# Mainboard_2.net
KiCad netlist of a schematic drawn in Altium Designer
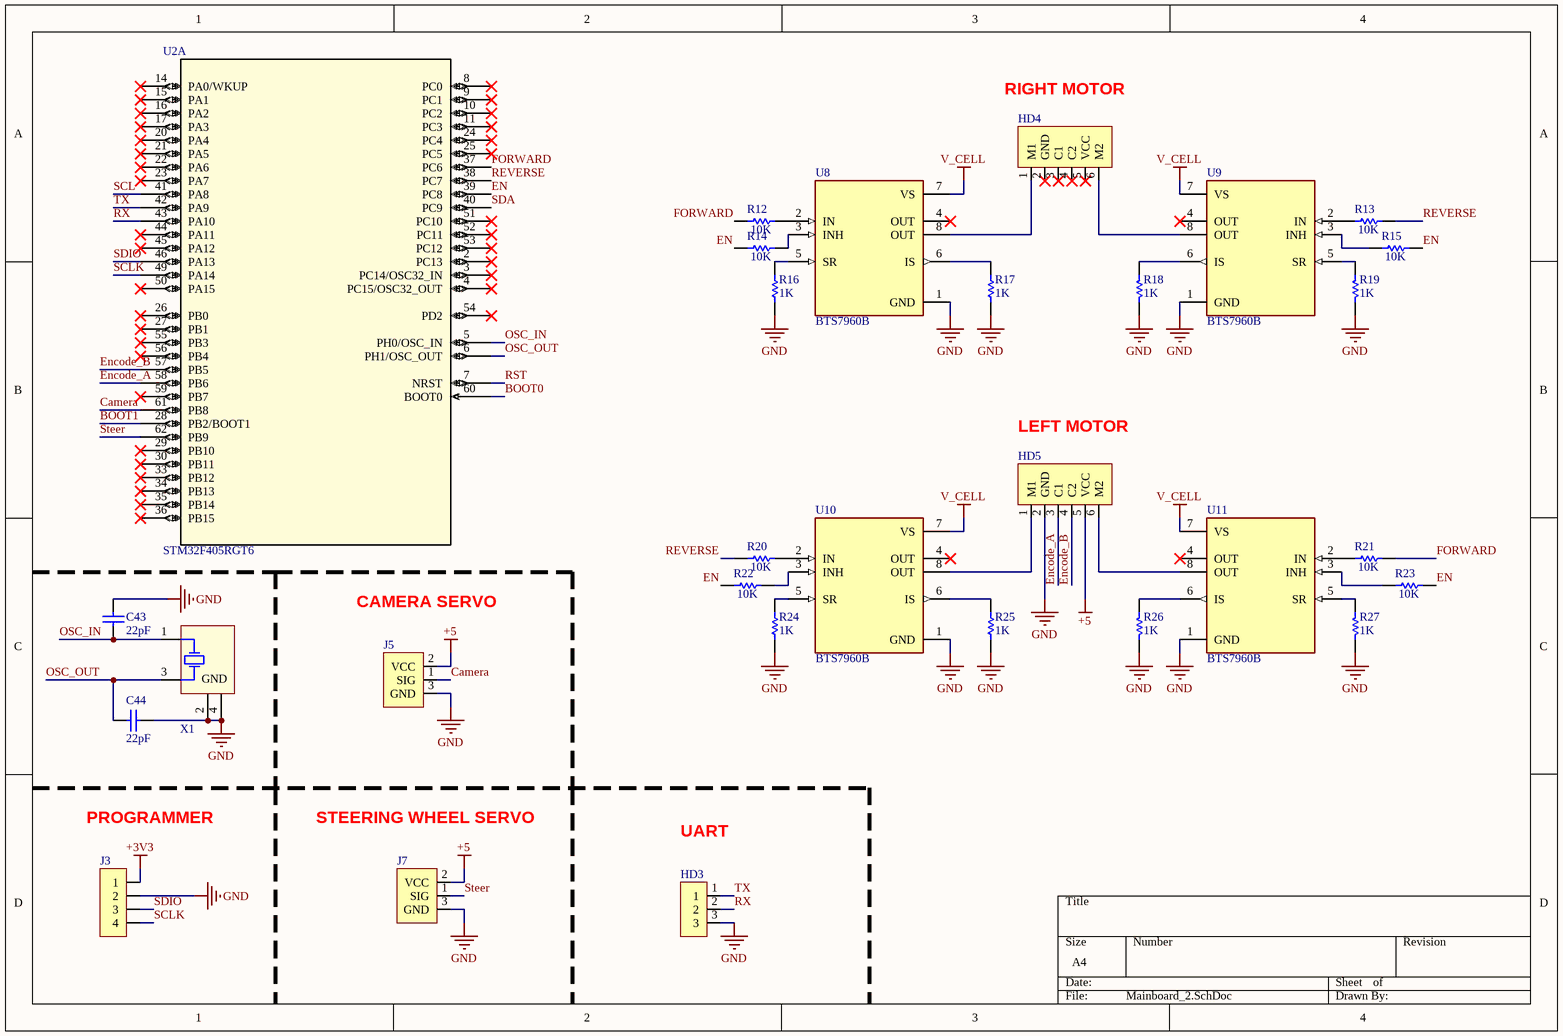
[diagram p0: Mainboard_2.SchDoc]

(export (version "E")
  (design (tool "Eeschema 10.0.6"))
  (components
    (comp (ref "C43")
      (value "22pF")
      (footprint "6-0805_M")
      (description "Capacitor")
      (fields (field (name "PUBLISHER") "Altium Limited"))
      (libsource (lib "Miscellaneous Devices") (part "Cap"))
    )
    (comp (ref "C44")
      (value "22pF")
      (footprint "6-0805_M")
      (description "Capacitor")
      (fields (field (name "PUBLISHER") "Altium Limited"))
      (libsource (lib "Miscellaneous Devices") (part "Cap"))
    )
    (comp (ref "HD3")
      (value "3_pin conn")
      (footprint "3-pin XHB_2.54")
      (libsource (lib "KHAI_LIB") (part "3_pin conn"))
    )
    (comp (ref "HD4")
      (value "6-pin connnector (Encoder DC motor 2mm)")
      (footprint "6_PIN MOTOR")
      (libsource (lib "KHAI_LIB") (part "6-pin connnector (Encoder DC motor 2.54mm)"))
    )
    (comp (ref "HD5")
      (value "6-pin connnector (Encoder DC motor 2mm)")
      (footprint "6_PIN MOTOR")
      (libsource (lib "KHAI_LIB") (part "6-pin connnector (Encoder DC motor 2.54mm)"))
    )
    (comp (ref "J3")
      (value "4_pin connector")
      (footprint "4_PIN 2.54mm")
      (libsource (lib "KHAI_LIB") (part "4_pin connector"))
    )
    (comp (ref "J5")
      (value "3_pin steering wheel")
      (footprint "3_PIN SERVO CONNECTOR")
      (libsource (lib "KHAI_LIB") (part "3_pin steering wheel"))
    )
    (comp (ref "J7")
      (value "3_pin steering wheel")
      (footprint "3_PIN SERVO CONNECTOR")
      (libsource (lib "KHAI_LIB") (part "3_pin steering wheel"))
    )
    (comp (ref "R12")
      (value "10K")
      (footprint "6-0805_N")
      (description "Resistor")
      (fields (field (name "PUBLISHER") "Altium Limited"))
      (libsource (lib "Miscellaneous Devices") (part "Res1"))
    )
    (comp (ref "R13")
      (value "10K")
      (footprint "6-0805_N")
      (description "Resistor")
      (fields (field (name "PUBLISHER") "Altium Limited"))
      (libsource (lib "Miscellaneous Devices") (part "Res1"))
    )
    (comp (ref "R14")
      (value "10K")
      (footprint "6-0805_N")
      (description "Resistor")
      (fields (field (name "PUBLISHER") "Altium Limited"))
      (libsource (lib "Miscellaneous Devices") (part "Res1"))
    )
    (comp (ref "R15")
      (value "10K")
      (footprint "6-0805_N")
      (description "Resistor")
      (fields (field (name "PUBLISHER") "Altium Limited"))
      (libsource (lib "Miscellaneous Devices") (part "Res1"))
    )
    (comp (ref "R16")
      (value "1K")
      (footprint "6-0805_N")
      (description "Resistor")
      (fields (field (name "PUBLISHER") "Altium Limited"))
      (libsource (lib "Miscellaneous Devices") (part "Res1"))
    )
    (comp (ref "R17")
      (value "1K")
      (footprint "6-0805_N")
      (description "Resistor")
      (fields (field (name "PUBLISHER") "Altium Limited"))
      (libsource (lib "Miscellaneous Devices") (part "Res1"))
    )
    (comp (ref "R18")
      (value "1K")
      (footprint "6-0805_N")
      (description "Resistor")
      (fields (field (name "PUBLISHER") "Altium Limited"))
      (libsource (lib "Miscellaneous Devices") (part "Res1"))
    )
    (comp (ref "R19")
      (value "1K")
      (footprint "6-0805_N")
      (description "Resistor")
      (fields (field (name "PUBLISHER") "Altium Limited"))
      (libsource (lib "Miscellaneous Devices") (part "Res1"))
    )
    (comp (ref "R20")
      (value "10K")
      (footprint "6-0805_N")
      (description "Resistor")
      (fields (field (name "PUBLISHER") "Altium Limited"))
      (libsource (lib "Miscellaneous Devices") (part "Res1"))
    )
    (comp (ref "R21")
      (value "10K")
      (footprint "6-0805_N")
      (description "Resistor")
      (fields (field (name "PUBLISHER") "Altium Limited"))
      (libsource (lib "Miscellaneous Devices") (part "Res1"))
    )
    (comp (ref "R22")
      (value "10K")
      (footprint "6-0805_N")
      (description "Resistor")
      (fields (field (name "PUBLISHER") "Altium Limited"))
      (libsource (lib "Miscellaneous Devices") (part "Res1"))
    )
    (comp (ref "R23")
      (value "10K")
      (footprint "6-0805_N")
      (description "Resistor")
      (fields (field (name "PUBLISHER") "Altium Limited"))
      (libsource (lib "Miscellaneous Devices") (part "Res1"))
    )
    (comp (ref "R24")
      (value "1K")
      (footprint "6-0805_N")
      (description "Resistor")
      (fields (field (name "PUBLISHER") "Altium Limited"))
      (libsource (lib "Miscellaneous Devices") (part "Res1"))
    )
    (comp (ref "R25")
      (value "1K")
      (footprint "6-0805_N")
      (description "Resistor")
      (fields (field (name "PUBLISHER") "Altium Limited"))
      (libsource (lib "Miscellaneous Devices") (part "Res1"))
    )
    (comp (ref "R26")
      (value "1K")
      (footprint "6-0805_N")
      (description "Resistor")
      (fields (field (name "PUBLISHER") "Altium Limited"))
      (libsource (lib "Miscellaneous Devices") (part "Res1"))
    )
    (comp (ref "R27")
      (value "1K")
      (footprint "6-0805_N")
      (description "Resistor")
      (fields (field (name "PUBLISHER") "Altium Limited"))
      (libsource (lib "Miscellaneous Devices") (part "Res1"))
    )
    (comp (ref "U2")
      (value "STM32F405RGT6")
      (footprint "LQFP64-10x10mm")
      (fields (field (name "COPYRIGHT") "Copyright (C) 2025 Ultra Librarian. All rights reserved."))
      (libsource (lib "STM32F405RGT6") (part "STM32F405RGT6"))
    )
    (comp (ref "U8")
      (value "BTS7960B")
      (footprint "DPAK127P1490X440-8N")
      (description "Half Bridge Driver DC Motors, General Purpose DMOS PG-TO263-7-1")
      (fields (field (name "MF") "Infineon"))
      (libsource (lib "") (part "BTS7960B_1"))
    )
    (comp (ref "U9")
      (value "BTS7960B")
      (footprint "DPAK127P1490X440-8N")
      (description "Half Bridge Driver DC Motors, General Purpose DMOS PG-TO263-7-1")
      (fields (field (name "MF") "Infineon"))
      (libsource (lib "KHAI_LIB") (part "BTS7960B"))
    )
    (comp (ref "U10")
      (value "BTS7960B")
      (footprint "DPAK127P1490X440-8N")
      (description "Half Bridge Driver DC Motors, General Purpose DMOS PG-TO263-7-1")
      (fields (field (name "MF") "Infineon"))
      (libsource (lib "") (part "BTS7960B_1"))
    )
    (comp (ref "U11")
      (value "BTS7960B")
      (footprint "DPAK127P1490X440-8N")
      (description "Half Bridge Driver DC Motors, General Purpose DMOS PG-TO263-7-1")
      (fields (field (name "MF") "Infineon"))
      (libsource (lib "KHAI_LIB") (part "BTS7960B"))
    )
    (comp (ref "X1")
      (value "XT4")
      (footprint "XT4-SMD")
      (description "Crystal, 16 MHz, -30 to 85 degC, 3.2 x 2.5 x 0.9 mm SMD")
      (libsource (lib "LIBRARY") (part "XT4"))
    )
  )
  (nets
    (net (code "1") (name "+3V3") (class "Default")
      (node (ref "J3") (pin "1") (pinfunction "1_1") (pintype "passive"))
    )
    (net (code "2") (name "+5") (class "Default")
      (node (ref "HD5") (pin "5") (pinfunction "VCC_5") (pintype "passive"))
      (node (ref "J5") (pin "2") (pinfunction "VCC_2") (pintype "passive"))
      (node (ref "J7") (pin "2") (pinfunction "VCC_2") (pintype "passive"))
    )
    (net (code "3") (name "/BOOT0") (class "Default")
      (node (ref "U2") (pin "60") (pinfunction "BOOT0_60") (pintype "input"))
    )
    (net (code "4") (name "/BOOT1") (class "Default")
      (node (ref "U2") (pin "28") (pinfunction "PB2/BOOT1_28") (pintype "bidirectional"))
    )
    (net (code "5") (name "/Camera") (class "Default")
      (node (ref "J5") (pin "1") (pinfunction "SIG_1") (pintype "passive"))
      (node (ref "U2") (pin "61") (pinfunction "PB8_61") (pintype "bidirectional"))
    )
    (net (code "6") (name "/EN") (class "Default")
      (node (ref "R14") (pin "1") (pinfunction "1_1") (pintype "passive"))
      (node (ref "R15") (pin "2") (pinfunction "2_2") (pintype "passive"))
      (node (ref "R22") (pin "1") (pinfunction "1_1") (pintype "passive"))
      (node (ref "R23") (pin "2") (pinfunction "2_2") (pintype "passive"))
      (node (ref "U2") (pin "39") (pinfunction "PC8_39") (pintype "bidirectional"))
    )
    (net (code "7") (name "/Encode_A") (class "Default")
      (node (ref "HD5") (pin "3") (pinfunction "C1_3") (pintype "passive"))
      (node (ref "U2") (pin "58") (pinfunction "PB6_58") (pintype "bidirectional"))
    )
    (net (code "8") (name "/Encode_B") (class "Default")
      (node (ref "HD5") (pin "4") (pinfunction "C2_4") (pintype "passive"))
      (node (ref "U2") (pin "57") (pinfunction "PB5_57") (pintype "bidirectional"))
    )
    (net (code "9") (name "/FORWARD") (class "Default")
      (node (ref "R12") (pin "1") (pinfunction "1_1") (pintype "passive"))
      (node (ref "R21") (pin "2") (pinfunction "2_2") (pintype "passive"))
      (node (ref "U2") (pin "37") (pinfunction "PC6_37") (pintype "bidirectional"))
    )
    (net (code "10") (name "/OSC_IN") (class "Default")
      (node (ref "C43") (pin "2") (pinfunction "2_2") (pintype "passive"))
      (node (ref "U2") (pin "5") (pinfunction "PH0/OSC_IN_5") (pintype "bidirectional"))
      (node (ref "X1") (pin "1") (pinfunction "XTAL_1") (pintype "passive"))
    )
    (net (code "11") (name "/OSC_OUT") (class "Default")
      (node (ref "C44") (pin "1") (pinfunction "1_1") (pintype "passive"))
      (node (ref "U2") (pin "6") (pinfunction "PH1/OSC_OUT_6") (pintype "bidirectional"))
      (node (ref "X1") (pin "3") (pinfunction "XTAL_3") (pintype "passive"))
    )
    (net (code "12") (name "/REVERSE") (class "Default")
      (node (ref "R13") (pin "2") (pinfunction "2_2") (pintype "passive"))
      (node (ref "R20") (pin "1") (pinfunction "1_1") (pintype "passive"))
      (node (ref "U2") (pin "38") (pinfunction "PC7_38") (pintype "bidirectional"))
    )
    (net (code "13") (name "/RST") (class "Default")
      (node (ref "U2") (pin "7") (pinfunction "NRST_7") (pintype "bidirectional"))
    )
    (net (code "14") (name "/RX") (class "Default")
      (node (ref "HD3") (pin "2") (pinfunction "2_2") (pintype "passive"))
      (node (ref "U2") (pin "43") (pinfunction "PA10_43") (pintype "bidirectional"))
    )
    (net (code "15") (name "/SCL") (class "Default")
      (node (ref "U2") (pin "41") (pinfunction "PA8_41") (pintype "bidirectional"))
    )
    (net (code "16") (name "/SCLK") (class "Default")
      (node (ref "J3") (pin "4") (pinfunction "4_4") (pintype "passive"))
      (node (ref "U2") (pin "49") (pinfunction "PA14_49") (pintype "bidirectional"))
    )
    (net (code "17") (name "/SDA") (class "Default")
      (node (ref "U2") (pin "40") (pinfunction "PC9_40") (pintype "bidirectional"))
    )
    (net (code "18") (name "/SDIO") (class "Default")
      (node (ref "J3") (pin "3") (pinfunction "3_3") (pintype "passive"))
      (node (ref "U2") (pin "46") (pinfunction "PA13_46") (pintype "bidirectional"))
    )
    (net (code "19") (name "/Steer") (class "Default")
      (node (ref "J7") (pin "1") (pinfunction "SIG_1") (pintype "passive"))
      (node (ref "U2") (pin "62") (pinfunction "PB9_62") (pintype "bidirectional"))
    )
    (net (code "20") (name "/TX") (class "Default")
      (node (ref "HD3") (pin "1") (pinfunction "1_1") (pintype "passive"))
      (node (ref "U2") (pin "42") (pinfunction "PA9_42") (pintype "bidirectional"))
    )
    (net (code "21") (name "GND") (class "Default")
      (node (ref "C43") (pin "1") (pinfunction "1_1") (pintype "passive"))
      (node (ref "C44") (pin "2") (pinfunction "2_2") (pintype "passive"))
      (node (ref "HD3") (pin "3") (pinfunction "3_3") (pintype "passive"))
      (node (ref "HD5") (pin "2") (pinfunction "GND_2") (pintype "passive"))
      (node (ref "J3") (pin "2") (pinfunction "2_2") (pintype "passive"))
      (node (ref "J5") (pin "3") (pinfunction "GND_3") (pintype "passive"))
      (node (ref "J7") (pin "3") (pinfunction "GND_3") (pintype "passive"))
      (node (ref "R16") (pin "2") (pinfunction "2_2") (pintype "passive"))
      (node (ref "R17") (pin "2") (pinfunction "2_2") (pintype "passive"))
      (node (ref "R18") (pin "2") (pinfunction "2_2") (pintype "passive"))
      (node (ref "R19") (pin "2") (pinfunction "2_2") (pintype "passive"))
      (node (ref "R24") (pin "2") (pinfunction "2_2") (pintype "passive"))
      (node (ref "R25") (pin "2") (pinfunction "2_2") (pintype "passive"))
      (node (ref "R26") (pin "2") (pinfunction "2_2") (pintype "passive"))
      (node (ref "R27") (pin "2") (pinfunction "2_2") (pintype "passive"))
      (node (ref "U10") (pin "1") (pinfunction "GND_1") (pintype "power_in"))
      (node (ref "U11") (pin "1") (pinfunction "GND_1") (pintype "power_in"))
      (node (ref "U8") (pin "1") (pinfunction "GND_1") (pintype "power_in"))
      (node (ref "U9") (pin "1") (pinfunction "GND_1") (pintype "power_in"))
      (node (ref "X1") (pin "2") (pinfunction "GND_2") (pintype "power_in"))
      (node (ref "X1") (pin "4") (pinfunction "GND_4") (pintype "power_in"))
    )
    (net (code "22") (name "Net-(HD4-M1)") (class "Default")
      (node (ref "HD4") (pin "1") (pinfunction "M1_1") (pintype "passive"))
      (node (ref "U8") (pin "8") (pinfunction "OUT_8") (pintype "passive"))
    )
    (net (code "23") (name "Net-(HD4-M2)") (class "Default")
      (node (ref "HD4") (pin "6") (pinfunction "M2_6") (pintype "passive"))
      (node (ref "U9") (pin "8") (pinfunction "OUT_8") (pintype "passive"))
    )
    (net (code "24") (name "Net-(HD5-M1)") (class "Default")
      (node (ref "HD5") (pin "1") (pinfunction "M1_1") (pintype "passive"))
      (node (ref "U10") (pin "8") (pinfunction "OUT_8") (pintype "passive"))
    )
    (net (code "25") (name "Net-(HD5-M2)") (class "Default")
      (node (ref "HD5") (pin "6") (pinfunction "M2_6") (pintype "passive"))
      (node (ref "U11") (pin "8") (pinfunction "OUT_8") (pintype "passive"))
    )
    (net (code "26") (name "Net-(U8-IN)") (class "Default")
      (node (ref "R12") (pin "2") (pinfunction "2_2") (pintype "passive"))
      (node (ref "U8") (pin "2") (pinfunction "IN_2") (pintype "input"))
    )
    (net (code "27") (name "Net-(U8-INH)") (class "Default")
      (node (ref "R14") (pin "2") (pinfunction "2_2") (pintype "passive"))
      (node (ref "U8") (pin "3") (pinfunction "INH_3") (pintype "input"))
    )
    (net (code "28") (name "Net-(U8-IS)") (class "Default")
      (node (ref "R17") (pin "1") (pinfunction "1_1") (pintype "passive"))
      (node (ref "U8") (pin "6") (pinfunction "IS_6") (pintype "output"))
    )
    (net (code "29") (name "Net-(U8-SR)") (class "Default")
      (node (ref "R16") (pin "1") (pinfunction "1_1") (pintype "passive"))
      (node (ref "U8") (pin "5") (pinfunction "SR_5") (pintype "input"))
    )
    (net (code "30") (name "Net-(U9-IN)") (class "Default")
      (node (ref "R13") (pin "1") (pinfunction "1_1") (pintype "passive"))
      (node (ref "U9") (pin "2") (pinfunction "IN_2") (pintype "input"))
    )
    (net (code "31") (name "Net-(U9-INH)") (class "Default")
      (node (ref "R15") (pin "1") (pinfunction "1_1") (pintype "passive"))
      (node (ref "U9") (pin "3") (pinfunction "INH_3") (pintype "input"))
    )
    (net (code "32") (name "Net-(U9-IS)") (class "Default")
      (node (ref "R18") (pin "1") (pinfunction "1_1") (pintype "passive"))
      (node (ref "U9") (pin "6") (pinfunction "IS_6") (pintype "output"))
    )
    (net (code "33") (name "Net-(U9-SR)") (class "Default")
      (node (ref "R19") (pin "1") (pinfunction "1_1") (pintype "passive"))
      (node (ref "U9") (pin "5") (pinfunction "SR_5") (pintype "input"))
    )
    (net (code "34") (name "Net-(U10-IN)") (class "Default")
      (node (ref "R20") (pin "2") (pinfunction "2_2") (pintype "passive"))
      (node (ref "U10") (pin "2") (pinfunction "IN_2") (pintype "input"))
    )
    (net (code "35") (name "Net-(U10-INH)") (class "Default")
      (node (ref "R22") (pin "2") (pinfunction "2_2") (pintype "passive"))
      (node (ref "U10") (pin "3") (pinfunction "INH_3") (pintype "input"))
    )
    (net (code "36") (name "Net-(U10-IS)") (class "Default")
      (node (ref "R25") (pin "1") (pinfunction "1_1") (pintype "passive"))
      (node (ref "U10") (pin "6") (pinfunction "IS_6") (pintype "output"))
    )
    (net (code "37") (name "Net-(U10-SR)") (class "Default")
      (node (ref "R24") (pin "1") (pinfunction "1_1") (pintype "passive"))
      (node (ref "U10") (pin "5") (pinfunction "SR_5") (pintype "input"))
    )
    (net (code "38") (name "Net-(U11-IN)") (class "Default")
      (node (ref "R21") (pin "1") (pinfunction "1_1") (pintype "passive"))
      (node (ref "U11") (pin "2") (pinfunction "IN_2") (pintype "input"))
    )
    (net (code "39") (name "Net-(U11-INH)") (class "Default")
      (node (ref "R23") (pin "1") (pinfunction "1_1") (pintype "passive"))
      (node (ref "U11") (pin "3") (pinfunction "INH_3") (pintype "input"))
    )
    (net (code "40") (name "Net-(U11-IS)") (class "Default")
      (node (ref "R26") (pin "1") (pinfunction "1_1") (pintype "passive"))
      (node (ref "U11") (pin "6") (pinfunction "IS_6") (pintype "output"))
    )
    (net (code "41") (name "Net-(U11-SR)") (class "Default")
      (node (ref "R27") (pin "1") (pinfunction "1_1") (pintype "passive"))
      (node (ref "U11") (pin "5") (pinfunction "SR_5") (pintype "input"))
    )
    (net (code "42") (name "V_CELL") (class "Default")
      (node (ref "U10") (pin "7") (pinfunction "VS_7") (pintype "power_in"))
      (node (ref "U11") (pin "7") (pinfunction "VS_7") (pintype "power_in"))
      (node (ref "U8") (pin "7") (pinfunction "VS_7") (pintype "power_in"))
      (node (ref "U9") (pin "7") (pinfunction "VS_7") (pintype "power_in"))
    )
    (net (code "43") (name "unconnected-(HD4-C1-Pad3)") (class "Default")
      (node (ref "HD4") (pin "3") (pinfunction "C1_3") (pintype "passive+no_connect"))
    )
    (net (code "44") (name "unconnected-(HD4-C2-Pad4)") (class "Default")
      (node (ref "HD4") (pin "4") (pinfunction "C2_4") (pintype "passive+no_connect"))
    )
    (net (code "45") (name "unconnected-(HD4-GND-Pad2)") (class "Default")
      (node (ref "HD4") (pin "2") (pinfunction "GND_2") (pintype "passive+no_connect"))
    )
    (net (code "46") (name "unconnected-(HD4-VCC-Pad5)") (class "Default")
      (node (ref "HD4") (pin "5") (pinfunction "VCC_5") (pintype "passive+no_connect"))
    )
    (net (code "47") (name "unconnected-(U2A-PA0{slash}WKUP-Pad14)") (class "Default")
      (node (ref "U2") (pin "14") (pinfunction "PA0/WKUP_14") (pintype "bidirectional+no_connect"))
    )
    (net (code "48") (name "unconnected-(U2A-PA1-Pad15)") (class "Default")
      (node (ref "U2") (pin "15") (pinfunction "PA1_15") (pintype "bidirectional+no_connect"))
    )
    (net (code "49") (name "unconnected-(U2A-PA2-Pad16)") (class "Default")
      (node (ref "U2") (pin "16") (pinfunction "PA2_16") (pintype "bidirectional+no_connect"))
    )
    (net (code "50") (name "unconnected-(U2A-PA3-Pad17)") (class "Default")
      (node (ref "U2") (pin "17") (pinfunction "PA3_17") (pintype "bidirectional+no_connect"))
    )
    (net (code "51") (name "unconnected-(U2A-PA4-Pad20)") (class "Default")
      (node (ref "U2") (pin "20") (pinfunction "PA4_20") (pintype "bidirectional+no_connect"))
    )
    (net (code "52") (name "unconnected-(U2A-PA5-Pad21)") (class "Default")
      (node (ref "U2") (pin "21") (pinfunction "PA5_21") (pintype "bidirectional+no_connect"))
    )
    (net (code "53") (name "unconnected-(U2A-PA6-Pad22)") (class "Default")
      (node (ref "U2") (pin "22") (pinfunction "PA6_22") (pintype "bidirectional+no_connect"))
    )
    (net (code "54") (name "unconnected-(U2A-PA7-Pad23)") (class "Default")
      (node (ref "U2") (pin "23") (pinfunction "PA7_23") (pintype "bidirectional+no_connect"))
    )
    (net (code "55") (name "unconnected-(U2A-PA11-Pad44)") (class "Default")
      (node (ref "U2") (pin "44") (pinfunction "PA11_44") (pintype "bidirectional+no_connect"))
    )
    (net (code "56") (name "unconnected-(U2A-PA12-Pad45)") (class "Default")
      (node (ref "U2") (pin "45") (pinfunction "PA12_45") (pintype "bidirectional+no_connect"))
    )
    (net (code "57") (name "unconnected-(U2A-PA15-Pad50)") (class "Default")
      (node (ref "U2") (pin "50") (pinfunction "PA15_50") (pintype "bidirectional+no_connect"))
    )
    (net (code "58") (name "unconnected-(U2A-PB0-Pad26)") (class "Default")
      (node (ref "U2") (pin "26") (pinfunction "PB0_26") (pintype "bidirectional+no_connect"))
    )
    (net (code "59") (name "unconnected-(U2A-PB1-Pad27)") (class "Default")
      (node (ref "U2") (pin "27") (pinfunction "PB1_27") (pintype "bidirectional+no_connect"))
    )
    (net (code "60") (name "unconnected-(U2A-PB3-Pad55)") (class "Default")
      (node (ref "U2") (pin "55") (pinfunction "PB3_55") (pintype "bidirectional+no_connect"))
    )
    (net (code "61") (name "unconnected-(U2A-PB4-Pad56)") (class "Default")
      (node (ref "U2") (pin "56") (pinfunction "PB4_56") (pintype "bidirectional+no_connect"))
    )
    (net (code "62") (name "unconnected-(U2A-PB7-Pad59)") (class "Default")
      (node (ref "U2") (pin "59") (pinfunction "PB7_59") (pintype "bidirectional+no_connect"))
    )
    (net (code "63") (name "unconnected-(U2A-PB10-Pad29)") (class "Default")
      (node (ref "U2") (pin "29") (pinfunction "PB10_29") (pintype "bidirectional+no_connect"))
    )
    (net (code "64") (name "unconnected-(U2A-PB11-Pad30)") (class "Default")
      (node (ref "U2") (pin "30") (pinfunction "PB11_30") (pintype "bidirectional+no_connect"))
    )
    (net (code "65") (name "unconnected-(U2A-PB12-Pad33)") (class "Default")
      (node (ref "U2") (pin "33") (pinfunction "PB12_33") (pintype "bidirectional+no_connect"))
    )
    (net (code "66") (name "unconnected-(U2A-PB13-Pad34)") (class "Default")
      (node (ref "U2") (pin "34") (pinfunction "PB13_34") (pintype "bidirectional+no_connect"))
    )
    (net (code "67") (name "unconnected-(U2A-PB14-Pad35)") (class "Default")
      (node (ref "U2") (pin "35") (pinfunction "PB14_35") (pintype "bidirectional+no_connect"))
    )
    (net (code "68") (name "unconnected-(U2A-PB15-Pad36)") (class "Default")
      (node (ref "U2") (pin "36") (pinfunction "PB15_36") (pintype "bidirectional+no_connect"))
    )
    (net (code "69") (name "unconnected-(U2A-PC0-Pad8)") (class "Default")
      (node (ref "U2") (pin "8") (pinfunction "PC0_8") (pintype "bidirectional+no_connect"))
    )
    (net (code "70") (name "unconnected-(U2A-PC1-Pad9)") (class "Default")
      (node (ref "U2") (pin "9") (pinfunction "PC1_9") (pintype "bidirectional+no_connect"))
    )
    (net (code "71") (name "unconnected-(U2A-PC2-Pad10)") (class "Default")
      (node (ref "U2") (pin "10") (pinfunction "PC2_10") (pintype "bidirectional+no_connect"))
    )
    (net (code "72") (name "unconnected-(U2A-PC3-Pad11)") (class "Default")
      (node (ref "U2") (pin "11") (pinfunction "PC3_11") (pintype "bidirectional+no_connect"))
    )
    (net (code "73") (name "unconnected-(U2A-PC4-Pad24)") (class "Default")
      (node (ref "U2") (pin "24") (pinfunction "PC4_24") (pintype "bidirectional+no_connect"))
    )
    (net (code "74") (name "unconnected-(U2A-PC5-Pad25)") (class "Default")
      (node (ref "U2") (pin "25") (pinfunction "PC5_25") (pintype "bidirectional+no_connect"))
    )
    (net (code "75") (name "unconnected-(U2A-PC10-Pad51)") (class "Default")
      (node (ref "U2") (pin "51") (pinfunction "PC10_51") (pintype "bidirectional+no_connect"))
    )
    (net (code "76") (name "unconnected-(U2A-PC11-Pad52)") (class "Default")
      (node (ref "U2") (pin "52") (pinfunction "PC11_52") (pintype "bidirectional+no_connect"))
    )
    (net (code "77") (name "unconnected-(U2A-PC12-Pad53)") (class "Default")
      (node (ref "U2") (pin "53") (pinfunction "PC12_53") (pintype "bidirectional+no_connect"))
    )
    (net (code "78") (name "unconnected-(U2A-PC13-Pad2)") (class "Default")
      (node (ref "U2") (pin "2") (pinfunction "PC13_2") (pintype "bidirectional+no_connect"))
    )
    (net (code "79") (name "unconnected-(U2A-PC14{slash}OSC32_IN-Pad3)") (class "Default")
      (node (ref "U2") (pin "3") (pinfunction "PC14/OSC32_IN_3") (pintype "bidirectional+no_connect"))
    )
    (net (code "80") (name "unconnected-(U2A-PC15{slash}OSC32_OUT-Pad4)") (class "Default")
      (node (ref "U2") (pin "4") (pinfunction "PC15/OSC32_OUT_4") (pintype "bidirectional+no_connect"))
    )
    (net (code "81") (name "unconnected-(U2A-PD2-Pad54)") (class "Default")
      (node (ref "U2") (pin "54") (pinfunction "PD2_54") (pintype "bidirectional+no_connect"))
    )
    (net (code "82") (name "unconnected-(U8-OUT-Pad4)") (class "Default")
      (node (ref "U8") (pin "4") (pinfunction "OUT_4") (pintype "passive+no_connect"))
    )
    (net (code "83") (name "unconnected-(U9-OUT-Pad4)") (class "Default")
      (node (ref "U9") (pin "4") (pinfunction "OUT_4") (pintype "passive+no_connect"))
    )
    (net (code "84") (name "unconnected-(U10-OUT-Pad4)") (class "Default")
      (node (ref "U10") (pin "4") (pinfunction "OUT_4") (pintype "passive+no_connect"))
    )
    (net (code "85") (name "unconnected-(U11-OUT-Pad4)") (class "Default")
      (node (ref "U11") (pin "4") (pinfunction "OUT_4") (pintype "passive+no_connect"))
    )
  )
)
